# ADC.net
KiCad netlist of a schematic drawn in Altium Designer
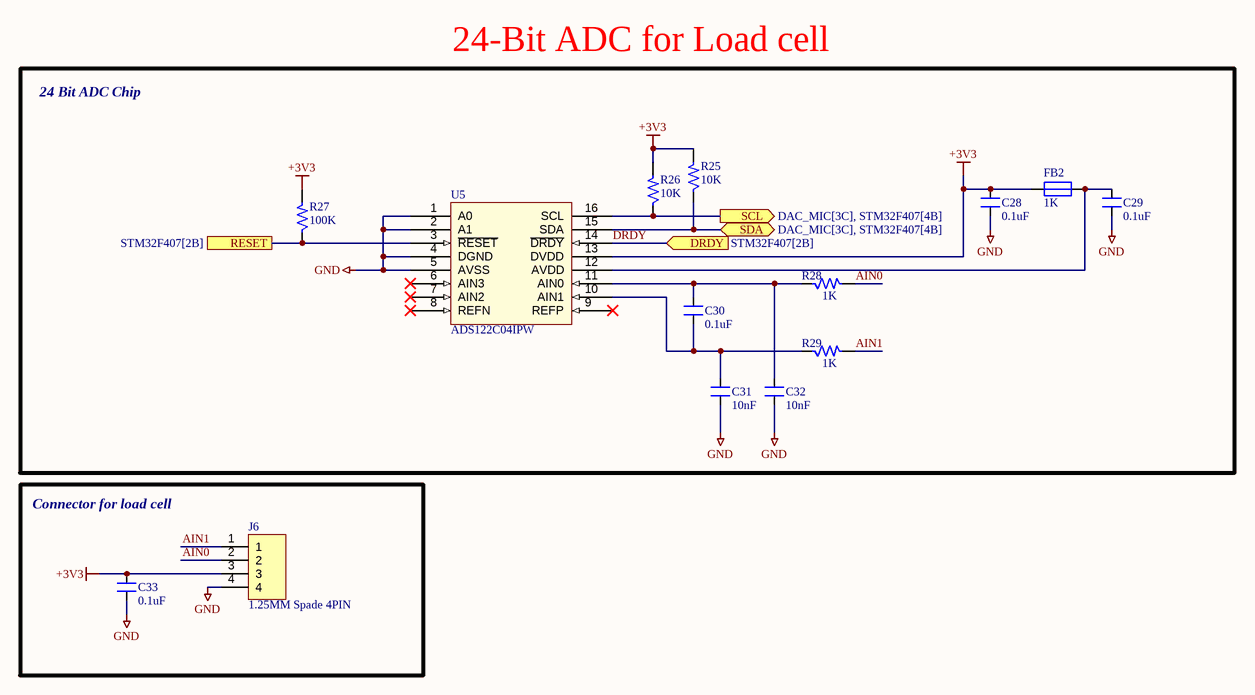
[diagram p0: ADC.SchDoc]

(export (version "E")
  (design (tool "Eeschema 10.0.6"))
  (components
    (comp (ref "C28")
      (value "0.1uF")
      (footprint "CAP_0805")
      (description "0.1µF ±5% 50V Ceramic Capacitor X7R 0805 (2012 Metric)")
      (fields
        (field (name "MANUFACTURER") "AVX Corporation")
        (field (name "MANUFACTURER PART NUMBER") "08055C104JAT4A")
      )
      (libsource (lib "ESTEEMPCBLIB") (part "CAP_0.1uF-50V-5%-0805"))
    )
    (comp (ref "C29")
      (value "0.1uF")
      (footprint "CAP_0805")
      (description "0.1µF ±5% 50V Ceramic Capacitor X7R 0805 (2012 Metric)")
      (fields
        (field (name "MANUFACTURER") "AVX Corporation")
        (field (name "MANUFACTURER PART NUMBER") "08055C104JAT4A")
      )
      (libsource (lib "ESTEEMPCBLIB") (part "CAP_0.1uF-50V-5%-0805"))
    )
    (comp (ref "C30")
      (value "0.1uF")
      (footprint "CAP_0805")
      (description "0.1µF ±5% 50V Ceramic Capacitor X7R 0805 (2012 Metric)")
      (fields
        (field (name "MANUFACTURER") "AVX Corporation")
        (field (name "MANUFACTURER PART NUMBER") "08055C104JAT4A")
      )
      (libsource (lib "ESTEEMPCBLIB") (part "CAP_0.1uF-50V-5%-0805"))
    )
    (comp (ref "C31")
      (value "10nF")
      (footprint "CAP_0805")
      (description "10000pF ±10% 50V Ceramic Capacitor X7R 0805 (2012 Metric)")
      (fields
        (field (name "MANUFACTURER") "Samsung")
        (field (name "MANUFACTURER PART NUMBER") "C0805C103K5RECAUTO")
      )
      (libsource (lib "ESTEEMPCBLIB") (part "CAP_10nF-50V-10%-0805"))
    )
    (comp (ref "C32")
      (value "10nF")
      (footprint "CAP_0805")
      (description "10000pF ±10% 50V Ceramic Capacitor X7R 0805 (2012 Metric)")
      (fields
        (field (name "MANUFACTURER") "Samsung")
        (field (name "MANUFACTURER PART NUMBER") "C0805C103K5RECAUTO")
      )
      (libsource (lib "ESTEEMPCBLIB") (part "CAP_10nF-50V-10%-0805"))
    )
    (comp (ref "C33")
      (value "0.1uF")
      (footprint "CAP_0805")
      (description "0.1µF ±5% 50V Ceramic Capacitor X7R 0805 (2012 Metric)")
      (fields
        (field (name "MANUFACTURER") "AVX Corporation")
        (field (name "MANUFACTURER PART NUMBER") "08055C104JAT4A")
      )
      (libsource (lib "ESTEEMPCBLIB") (part "CAP_0.1uF-50V-5%-0805"))
    )
    (comp (ref "FB2")
      (value "1K")
      (footprint "IND_0805")
      (description "1 kOhms @ 100MHz 1 Power Line Ferrite Bead 0805 (2012 Metric) 1.6A")
      (fields
        (field (name "MANUFACTURER") "Laird")
        (field (name "MANUFACTURER PART NUMBER") "BLM21SP102SH1D")
      )
      (libsource (lib "ESTEEMPCBLIB") (part "FB_1K-100MHZ-1.6A-0805"))
    )
    (comp (ref "J6")
      (value "1.25MM Spade 4PIN")
      (footprint "CON4_50_653004117322_TH_RA")
      (description "4 Pins, 1 Row 1.25mm Pitch, right angle Connector, male")
      (fields (field (name "MANUFACTURER PART NUMBER") "653004117322") (field (name "MANUFACTURER") "JST"))
      (libsource (lib "ESTEEMPCBLIB") (part "CON-PLG_4X1-50-RA-TH"))
    )
    (comp (ref "R25")
      (value "10K")
      (footprint "RES_0603")
      (description "10 kOhms ±1% 0.1W, 1/10W Chip Resistor 0603 (1608 Metric) Automotive AEC-Q200 Thick Film")
      (fields (field (name "MANUFACTURER") "Walsin") (field (name "MANUFACTURER PART NUMBER") "WR06X1002FTL"))
      (libsource (lib "ESTEEMPCBLIB") (part "RES_10K-0.1W-1%-0603"))
    )
    (comp (ref "R26")
      (value "10K")
      (footprint "RES_0603")
      (description "10 kOhms ±1% 0.1W, 1/10W Chip Resistor 0603 (1608 Metric) Automotive AEC-Q200 Thick Film")
      (fields (field (name "MANUFACTURER") "Walsin") (field (name "MANUFACTURER PART NUMBER") "WR06X1002FTL"))
      (libsource (lib "ESTEEMPCBLIB") (part "RES_10K-0.1W-1%-0603"))
    )
    (comp (ref "R27")
      (value "100K")
      (footprint "RES_0603")
      (description "100 kOhms ±1% 0.1W, 1/10W Chip Resistor 0603 (1608 Metric) Automotive AEC-Q200 Thick Film")
      (fields
        (field (name "MANUFACTURER") "Stackpole Electronics")
        (field (name "MANUFACTURER PART NUMBER") "RMCF0603FT100K")
      )
      (libsource (lib "ESTEEMPCBLIB") (part "RES_100K-0.1W-1%-0603"))
    )
    (comp (ref "R28")
      (value "1K")
      (footprint "RES_0603")
      (description "1 kOhms ±1% 0.1W, 1/10W Chip Resistor 0603 (1608 Metric) Automotive AEC-Q200 Thick Film")
      (fields (field (name "MANUFACTURER") "Walsin") (field (name "MANUFACTURER PART NUMBER") "WR06X1001FTL"))
      (libsource (lib "ESTEEMPCBLIB") (part "RES_1K-0.1W-1%-0603"))
    )
    (comp (ref "R29")
      (value "1K")
      (footprint "RES_0603")
      (description "1 kOhms ±1% 0.1W, 1/10W Chip Resistor 0603 (1608 Metric) Automotive AEC-Q200 Thick Film")
      (fields (field (name "MANUFACTURER") "Walsin") (field (name "MANUFACTURER PART NUMBER") "WR06X1001FTL"))
      (libsource (lib "ESTEEMPCBLIB") (part "RES_1K-0.1W-1%-0603"))
    )
    (comp (ref "U5")
      (value "ADS122C04IPW")
      (footprint "TSSOP16_25-59_294_54X14_SMT")
      (description "24 Bit Analog to Digital Converter 4 Input 1 Sigma-Delta 16-TSSOP")
      (fields (field (name "MANUFACTURER") "Texas Instruments"))
      (libsource (lib "ESTEEMPCBLIB") (part "IC_ADS122C04IPW"))
    )
  )
  (nets
    (net (code "1") (name "+3V3") (class "Default")
      (node (ref "C28") (pin "2") (pinfunction "2_2") (pintype "passive"))
      (node (ref "C33") (pin "2") (pinfunction "2_2") (pintype "passive"))
      (node (ref "FB2") (pin "1") (pinfunction "1_1") (pintype "passive"))
      (node (ref "J6") (pin "3") (pinfunction "3_3") (pintype "passive"))
      (node (ref "R25") (pin "2") (pinfunction "2_2") (pintype "passive"))
      (node (ref "R26") (pin "2") (pinfunction "2_2") (pintype "passive"))
      (node (ref "R27") (pin "2") (pinfunction "2_2") (pintype "passive"))
      (node (ref "U5") (pin "13") (pinfunction "DVDD_13") (pintype "power_in"))
    )
    (net (code "2") (name "/AIN0") (class "Default")
      (node (ref "J6") (pin "2") (pinfunction "2_2") (pintype "passive"))
      (node (ref "R28") (pin "2") (pinfunction "2_2") (pintype "passive"))
    )
    (net (code "3") (name "/AIN1") (class "Default")
      (node (ref "J6") (pin "1") (pinfunction "1_1") (pintype "passive"))
      (node (ref "R29") (pin "2") (pinfunction "2_2") (pintype "passive"))
    )
    (net (code "4") (name "/DRDY") (class "Default")
      (node (ref "U5") (pin "14") (pinfunction "DRDY_14") (pintype "input"))
    )
    (net (code "5") (name "/RESET") (class "Default")
      (node (ref "R27") (pin "1") (pinfunction "1_1") (pintype "passive"))
      (node (ref "U5") (pin "3") (pinfunction "RESET_3") (pintype "input"))
    )
    (net (code "6") (name "/SCL") (class "Default")
      (node (ref "R26") (pin "1") (pinfunction "1_1") (pintype "passive"))
      (node (ref "U5") (pin "16") (pinfunction "SCL_16") (pintype "open_collector"))
    )
    (net (code "7") (name "/SDA") (class "Default")
      (node (ref "R25") (pin "1") (pinfunction "1_1") (pintype "passive"))
      (node (ref "U5") (pin "15") (pinfunction "SDA_15") (pintype "open_collector"))
    )
    (net (code "8") (name "GND") (class "Default")
      (node (ref "C28") (pin "1") (pinfunction "1_1") (pintype "passive"))
      (node (ref "C29") (pin "1") (pinfunction "1_1") (pintype "passive"))
      (node (ref "C31") (pin "2") (pinfunction "2_2") (pintype "passive"))
      (node (ref "C32") (pin "2") (pinfunction "2_2") (pintype "passive"))
      (node (ref "C33") (pin "1") (pinfunction "1_1") (pintype "passive"))
      (node (ref "J6") (pin "4") (pinfunction "4_4") (pintype "passive"))
      (node (ref "U5") (pin "1") (pinfunction "A0_1") (pintype "passive"))
      (node (ref "U5") (pin "2") (pinfunction "A1_2") (pintype "passive"))
      (node (ref "U5") (pin "4") (pinfunction "DGND_4") (pintype "power_in"))
      (node (ref "U5") (pin "5") (pinfunction "AVSS_5") (pintype "power_in"))
    )
    (net (code "9") (name "Net-(U5-AIN0)") (class "Default")
      (node (ref "C30") (pin "2") (pinfunction "2_2") (pintype "passive"))
      (node (ref "C32") (pin "1") (pinfunction "1_1") (pintype "passive"))
      (node (ref "R28") (pin "1") (pinfunction "1_1") (pintype "passive"))
      (node (ref "U5") (pin "11") (pinfunction "AIN0_11") (pintype "input"))
    )
    (net (code "10") (name "Net-(U5-AIN1)") (class "Default")
      (node (ref "C30") (pin "1") (pinfunction "1_1") (pintype "passive"))
      (node (ref "C31") (pin "1") (pinfunction "1_1") (pintype "passive"))
      (node (ref "R29") (pin "1") (pinfunction "1_1") (pintype "passive"))
      (node (ref "U5") (pin "10") (pinfunction "AIN1_10") (pintype "input"))
    )
    (net (code "11") (name "Net-(U5-AVDD)") (class "Default")
      (node (ref "C29") (pin "2") (pinfunction "2_2") (pintype "passive"))
      (node (ref "FB2") (pin "2") (pinfunction "2_2") (pintype "passive"))
      (node (ref "U5") (pin "12") (pinfunction "AVDD_12") (pintype "power_in"))
    )
    (net (code "12") (name "unconnected-(U5-AIN2-Pad7)") (class "Default")
      (node (ref "U5") (pin "7") (pinfunction "AIN2_7") (pintype "input+no_connect"))
    )
    (net (code "13") (name "unconnected-(U5-AIN3-Pad6)") (class "Default")
      (node (ref "U5") (pin "6") (pinfunction "AIN3_6") (pintype "input+no_connect"))
    )
    (net (code "14") (name "unconnected-(U5-REFN-Pad8)") (class "Default")
      (node (ref "U5") (pin "8") (pinfunction "REFN_8") (pintype "input+no_connect"))
    )
    (net (code "15") (name "unconnected-(U5-REFP-Pad9)") (class "Default")
      (node (ref "U5") (pin "9") (pinfunction "REFP_9") (pintype "input+no_connect"))
    )
  )
)
